# V1_0.net
KiCad netlist of a schematic drawn in Altium Designer
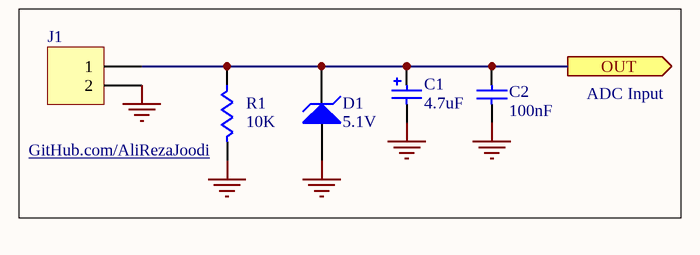
[diagram p0: V1.0.SchDoc]

(export (version "E")
  (design (tool "Eeschema 10.0.6"))
  (components
    (comp (ref "C1")
      (value "4.7uF")
      (footprint "CAPPR2.5-6.3x5")
      (description "Polarized Capacitor (Radial)")
      (fields (field (name "MANUFACTURER") "Generic Components") (field (name "PUBLISHER") "Altium Limited"))
      (libsource (lib "Miscellaneous Devices") (part "Cap Pol1"))
    )
    (comp (ref "C2")
      (value "100nF")
      (footprint "CAPNTO2.54-3.05x1.78A")
      (description "Capacitor")
      (fields (field (name "MANUFACTURER") "Generic Components") (field (name "PUBLISHER") "Altium Limited"))
      (libsource (lib "Miscellaneous Devices") (part "Cap"))
    )
    (comp (ref "D1")
      (value "5.1V")
      (footprint "DIODE0.4_Glass")
      (description "Zener Diode")
      (fields (field (name "MANUFACTURER") "Generic Components") (field (name "PUBLISHER") "Altium Limited"))
      (libsource (lib "Miscellaneous Devices") (part "D Zener"))
    )
    (comp (ref "J1")
      (value "Header 2")
      (footprint "Fonics_2PIN_1")
      (description "Header, 2-Pin")
      (fields (field (name "PUBLISHER") "Altium Limited"))
      (libsource (lib "Miscellaneous Connectors") (part "Header 2"))
    )
    (comp (ref "R1")
      (value "10K")
      (footprint "AXIAL-0.4")
      (description "Resistor")
      (fields (field (name "MANUFACTURER") "Generic Components") (field (name "PUBLISHER") "Altium Limited"))
      (libsource (lib "Miscellaneous Devices") (part "Res1"))
    )
  )
  (nets
    (net (code "1") (name "/OUT") (class "Default")
      (node (ref "C1") (pin "1") (pinfunction "1_1") (pintype "passive"))
      (node (ref "C2") (pin "2") (pinfunction "2_2") (pintype "passive"))
      (node (ref "D1") (pin "2") (pinfunction "K_2") (pintype "passive"))
      (node (ref "J1") (pin "1") (pinfunction "1_1") (pintype "passive"))
      (node (ref "R1") (pin "1") (pinfunction "1_1") (pintype "passive"))
    )
    (net (code "2") (name "GND") (class "Default")
      (node (ref "C1") (pin "2") (pinfunction "2_2") (pintype "passive"))
      (node (ref "C2") (pin "1") (pinfunction "1_1") (pintype "passive"))
      (node (ref "D1") (pin "1") (pinfunction "A_1") (pintype "passive"))
      (node (ref "J1") (pin "2") (pinfunction "2_2") (pintype "passive"))
      (node (ref "R1") (pin "2") (pinfunction "2_2") (pintype "passive"))
    )
  )
)
